# main_board.net
KiCad netlist of a schematic drawn in EAGLE
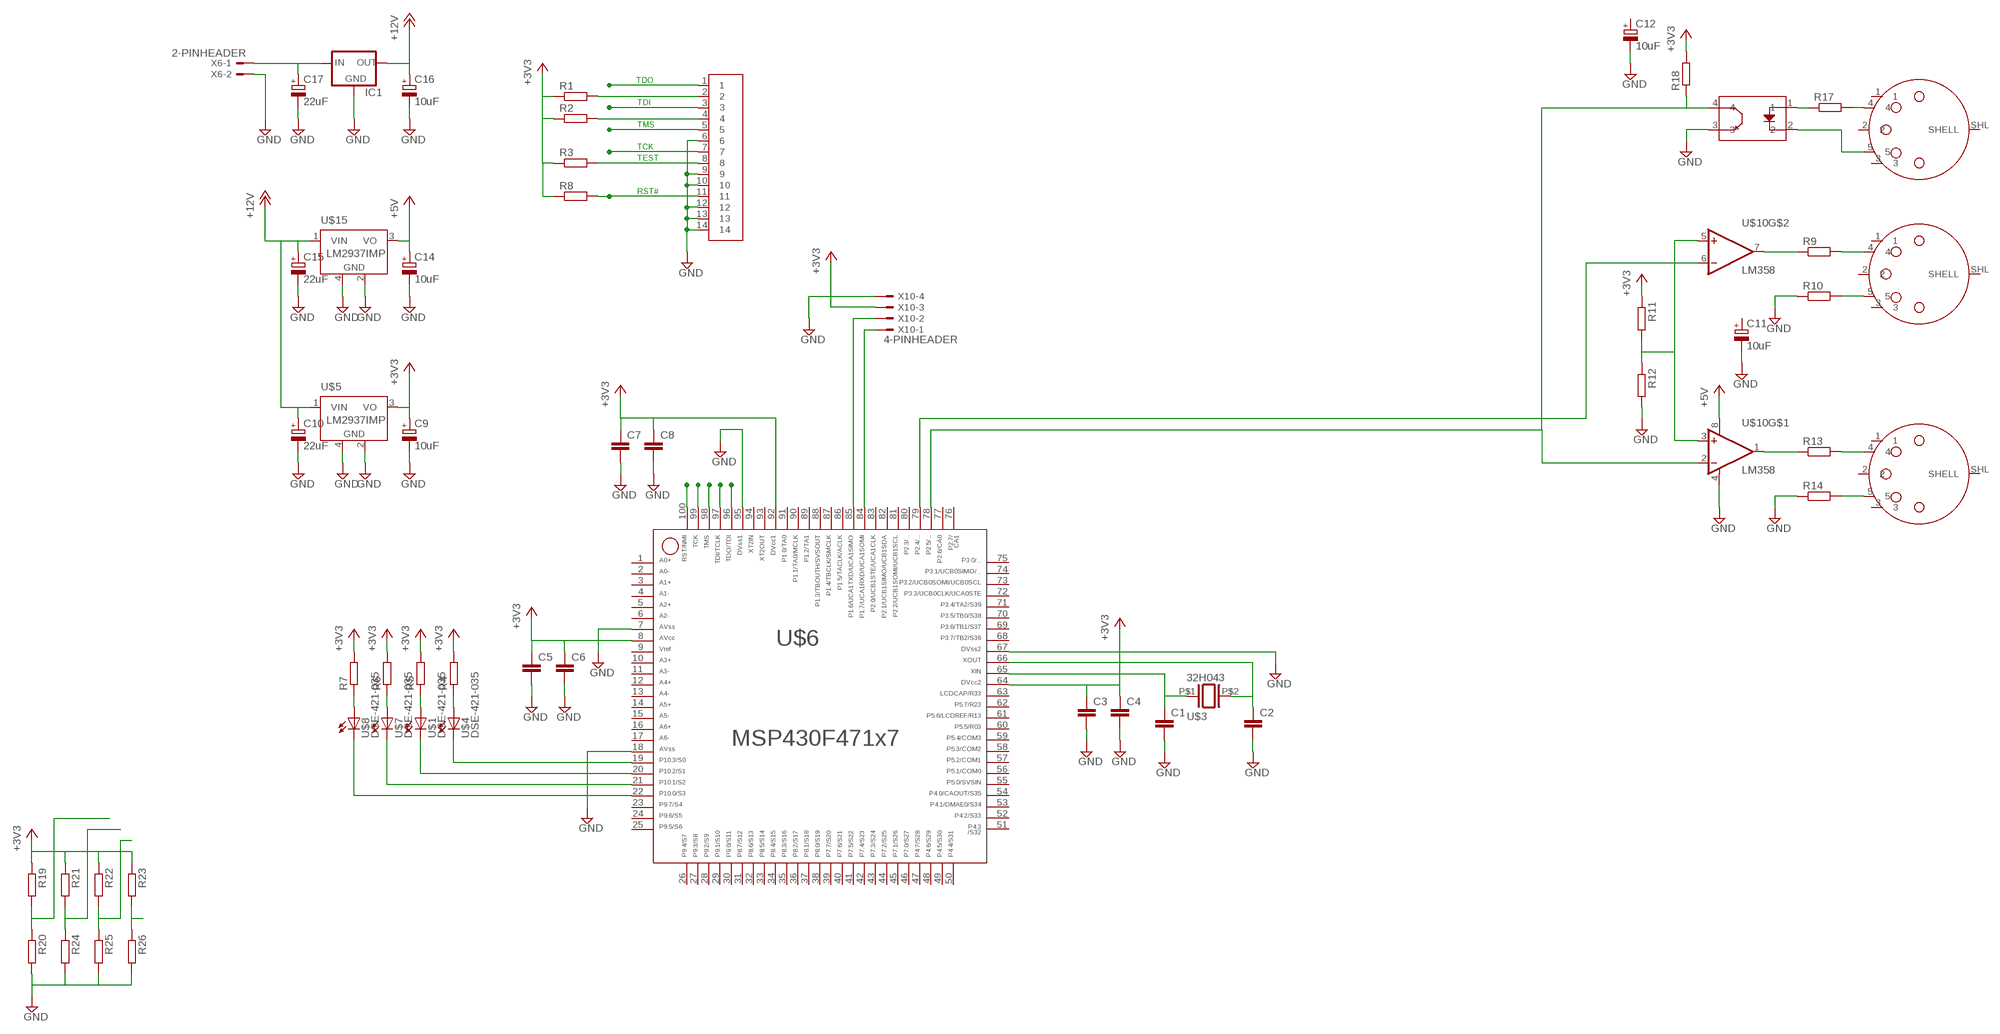
[diagram p0: schematic, sheet 1]

(export (version "E")
  (design (tool "Eeschema 10.0.6"))
  (components
    (comp (ref "C1")
      (value "C-EUC0402")
      (footprint "eagle-import:C0402")
      (libsource (lib "eagle-import") (part "C-EUC0402"))
    )
    (comp (ref "C2")
      (value "C-EUC0402")
      (footprint "eagle-import:C0402")
      (libsource (lib "eagle-import") (part "C-EUC0402"))
    )
    (comp (ref "C3")
      (value "C-EUC0402")
      (footprint "eagle-import:C0402")
      (libsource (lib "eagle-import") (part "C-EUC0402"))
    )
    (comp (ref "C4")
      (value "C-EUC0402")
      (footprint "eagle-import:C0402")
      (libsource (lib "eagle-import") (part "C-EUC0402"))
    )
    (comp (ref "C5")
      (value "C-EUC0402")
      (footprint "eagle-import:C0402")
      (libsource (lib "eagle-import") (part "C-EUC0402"))
    )
    (comp (ref "C6")
      (value "C-EUC0402")
      (footprint "eagle-import:C0402")
      (libsource (lib "eagle-import") (part "C-EUC0402"))
    )
    (comp (ref "C7")
      (value "C-EUC0402")
      (footprint "eagle-import:C0402")
      (libsource (lib "eagle-import") (part "C-EUC0402"))
    )
    (comp (ref "C8")
      (value "C-EUC0402")
      (footprint "eagle-import:C0402")
      (libsource (lib "eagle-import") (part "C-EUC0402"))
    )
    (comp (ref "C9")
      (value "10uF")
      (footprint "eagle-import:SMC_C")
      (libsource (lib "eagle-import") (part "CPOL-EUSMCC"))
    )
    (comp (ref "C10")
      (value "22uF")
      (footprint "eagle-import:SMC_D")
      (libsource (lib "eagle-import") (part "CPOL-EUSMCD"))
    )
    (comp (ref "C11")
      (value "10uF")
      (footprint "eagle-import:SMC_C")
      (libsource (lib "eagle-import") (part "CPOL-EUSMCC"))
    )
    (comp (ref "C12")
      (value "10uF")
      (footprint "eagle-import:SMC_C")
      (libsource (lib "eagle-import") (part "CPOL-EUSMCC"))
    )
    (comp (ref "C14")
      (value "10uF")
      (footprint "eagle-import:SMC_C")
      (libsource (lib "eagle-import") (part "CPOL-EUSMCC"))
    )
    (comp (ref "C15")
      (value "22uF")
      (footprint "eagle-import:SMC_D")
      (libsource (lib "eagle-import") (part "CPOL-EUSMCD"))
    )
    (comp (ref "C16")
      (value "10uF")
      (footprint "eagle-import:SMC_C")
      (libsource (lib "eagle-import") (part "CPOL-EUSMCC"))
    )
    (comp (ref "C17")
      (value "22uF")
      (footprint "eagle-import:SMC_D")
      (libsource (lib "eagle-import") (part "CPOL-EUSMCD"))
    )
    (comp (ref "IC1")
      (value "78MXXS")
      (footprint "eagle-import:78MXXS")
      (libsource (lib "eagle-import") (part "78MXXS"))
    )
    (comp (ref "R1")
      (value "R-EU_R0402")
      (footprint "eagle-import:R0402")
      (libsource (lib "eagle-import") (part "R-EU_R0402"))
    )
    (comp (ref "R2")
      (value "R-EU_R0402")
      (footprint "eagle-import:R0402")
      (libsource (lib "eagle-import") (part "R-EU_R0402"))
    )
    (comp (ref "R3")
      (value "R-EU_R0402")
      (footprint "eagle-import:R0402")
      (libsource (lib "eagle-import") (part "R-EU_R0402"))
    )
    (comp (ref "R4")
      (value "R-EU_R0402")
      (footprint "eagle-import:R0402")
      (libsource (lib "eagle-import") (part "R-EU_R0402"))
    )
    (comp (ref "R5")
      (value "R-EU_R0402")
      (footprint "eagle-import:R0402")
      (libsource (lib "eagle-import") (part "R-EU_R0402"))
    )
    (comp (ref "R6")
      (value "R-EU_R0402")
      (footprint "eagle-import:R0402")
      (libsource (lib "eagle-import") (part "R-EU_R0402"))
    )
    (comp (ref "R7")
      (value "R-EU_R0402")
      (footprint "eagle-import:R0402")
      (libsource (lib "eagle-import") (part "R-EU_R0402"))
    )
    (comp (ref "R8")
      (value "R-EU_R0402")
      (footprint "eagle-import:R0402")
      (libsource (lib "eagle-import") (part "R-EU_R0402"))
    )
    (comp (ref "R9")
      (value "R-EU_R1206")
      (footprint "eagle-import:R1206")
      (libsource (lib "eagle-import") (part "R-EU_R1206"))
    )
    (comp (ref "R10")
      (value "R-EU_R1206")
      (footprint "eagle-import:R1206")
      (libsource (lib "eagle-import") (part "R-EU_R1206"))
    )
    (comp (ref "R11")
      (value "R-EU_R0402")
      (footprint "eagle-import:R0402")
      (libsource (lib "eagle-import") (part "R-EU_R0402"))
    )
    (comp (ref "R12")
      (value "R-EU_R0402")
      (footprint "eagle-import:R0402")
      (libsource (lib "eagle-import") (part "R-EU_R0402"))
    )
    (comp (ref "R13")
      (value "R-EU_R1206")
      (footprint "eagle-import:R1206")
      (libsource (lib "eagle-import") (part "R-EU_R1206"))
    )
    (comp (ref "R14")
      (value "R-EU_R1206")
      (footprint "eagle-import:R1206")
      (libsource (lib "eagle-import") (part "R-EU_R1206"))
    )
    (comp (ref "R17")
      (value "R-EU_R1206")
      (footprint "eagle-import:R1206")
      (libsource (lib "eagle-import") (part "R-EU_R1206"))
    )
    (comp (ref "R18")
      (value "R-EU_R1206")
      (footprint "eagle-import:R1206")
      (libsource (lib "eagle-import") (part "R-EU_R1206"))
    )
    (comp (ref "R19")
      (value "R-EU_R0402")
      (footprint "eagle-import:R0402")
      (libsource (lib "eagle-import") (part "R-EU_R0402"))
    )
    (comp (ref "R20")
      (value "R-EU_R0402")
      (footprint "eagle-import:R0402")
      (libsource (lib "eagle-import") (part "R-EU_R0402"))
    )
    (comp (ref "R21")
      (value "R-EU_R0402")
      (footprint "eagle-import:R0402")
      (libsource (lib "eagle-import") (part "R-EU_R0402"))
    )
    (comp (ref "R22")
      (value "R-EU_R0402")
      (footprint "eagle-import:R0402")
      (libsource (lib "eagle-import") (part "R-EU_R0402"))
    )
    (comp (ref "R23")
      (value "R-EU_R0402")
      (footprint "eagle-import:R0402")
      (libsource (lib "eagle-import") (part "R-EU_R0402"))
    )
    (comp (ref "R24")
      (value "R-EU_R0402")
      (footprint "eagle-import:R0402")
      (libsource (lib "eagle-import") (part "R-EU_R0402"))
    )
    (comp (ref "R25")
      (value "R-EU_R0402")
      (footprint "eagle-import:R0402")
      (libsource (lib "eagle-import") (part "R-EU_R0402"))
    )
    (comp (ref "R26")
      (value "R-EU_R0402")
      (footprint "eagle-import:R0402")
      (libsource (lib "eagle-import") (part "R-EU_R0402"))
    )
    (comp (ref "U$1")
      (value "DSE-421-035")
      (footprint "eagle-import:2432")
      (libsource (lib "eagle-import") (part "DSE-421-035"))
    )
    (comp (ref "U$2")
      (value "2X7SMD_HEADER")
      (footprint "eagle-import:2X14SMDPADS")
      (libsource (lib "eagle-import") (part "2X7SMD_HEADER"))
    )
    (comp (ref "U$3")
      (value "32H043")
      (footprint "eagle-import:XTAL-SMALL-4")
      (libsource (lib "eagle-import") (part "32H043"))
    )
    (comp (ref "U$4")
      (value "DSE-421-035")
      (footprint "eagle-import:2432")
      (libsource (lib "eagle-import") (part "DSE-421-035"))
    )
    (comp (ref "U$5")
      (value "LM2937IMP")
      (footprint "eagle-import:SOT223")
      (libsource (lib "eagle-import") (part "LM2937IMP"))
    )
    (comp (ref "U$6")
      (value "F471X7---PZ100")
      (footprint "eagle-import:PZ100")
      (libsource (lib "eagle-import") (part "F471X7---PZ100"))
    )
    (comp (ref "U$7")
      (value "DSE-421-035")
      (footprint "eagle-import:2432")
      (libsource (lib "eagle-import") (part "DSE-421-035"))
    )
    (comp (ref "U$8")
      (value "DSE-421-035")
      (footprint "eagle-import:2432")
      (libsource (lib "eagle-import") (part "DSE-421-035"))
    )
    (comp (ref "U$9")
      (value "MIDI_VERT")
      (footprint "eagle-import:DIN-5_VERT")
      (libsource (lib "eagle-import") (part "MIDI_VERT"))
    )
    (comp (ref "U$10")
      (value "LM358")
      (footprint "eagle-import:SO08")
      (libsource (lib "eagle-import") (part "LM358"))
    )
    (comp (ref "U$11")
      (value "MIDI_VERT")
      (footprint "eagle-import:DIN-5_VERT")
      (libsource (lib "eagle-import") (part "MIDI_VERT"))
    )
    (comp (ref "U$15")
      (value "LM2937IMP")
      (footprint "eagle-import:SOT223")
      (libsource (lib "eagle-import") (part "LM2937IMP"))
    )
    (comp (ref "U$19")
      (value "F2801A")
      (footprint "eagle-import:LONG_TSOP")
      (libsource (lib "eagle-import") (part "F2801A"))
    )
    (comp (ref "U$20")
      (value "MIDI_VERT")
      (footprint "eagle-import:DIN-5_VERT")
      (libsource (lib "eagle-import") (part "MIDI_VERT"))
    )
    (comp (ref "X6")
      (value "2-PINHEADER")
      (footprint "eagle-import:22-23-2021")
      (fields (field (name "MF") "MOLEX") (field (name "MPN") "22-23-2021"))
      (libsource (lib "eagle-import") (part "2-PINHEADER"))
    )
    (comp (ref "X10")
      (value "4-PINHEADER")
      (footprint "eagle-import:22-23-2041")
      (fields (field (name "MF") "MOLEX") (field (name "MPN") "22-23-2041"))
      (libsource (lib "eagle-import") (part "4-PINHEADER"))
    )
  )
  (nets
    (net (code "1") (name "+3V3") (class "Default")
      (node (ref "C3") (pin "1") (pinfunction "1_1") (pintype "passive"))
      (node (ref "C4") (pin "1") (pinfunction "1_1") (pintype "passive"))
      (node (ref "C5") (pin "1") (pinfunction "1_1") (pintype "passive"))
      (node (ref "C6") (pin "1") (pinfunction "1_1") (pintype "passive"))
      (node (ref "C7") (pin "1") (pinfunction "1_1") (pintype "passive"))
      (node (ref "C8") (pin "1") (pinfunction "1_1") (pintype "passive"))
      (node (ref "C9") (pin "+") (pinfunction "+_+") (pintype "passive"))
      (node (ref "R1") (pin "1") (pinfunction "1_1") (pintype "passive"))
      (node (ref "R11") (pin "1") (pinfunction "1_1") (pintype "passive"))
      (node (ref "R18") (pin "2") (pinfunction "2_2") (pintype "passive"))
      (node (ref "R19") (pin "1") (pinfunction "1_1") (pintype "passive"))
      (node (ref "R2") (pin "1") (pinfunction "1_1") (pintype "passive"))
      (node (ref "R21") (pin "1") (pinfunction "1_1") (pintype "passive"))
      (node (ref "R22") (pin "1") (pinfunction "1_1") (pintype "passive"))
      (node (ref "R23") (pin "1") (pinfunction "1_1") (pintype "passive"))
      (node (ref "R3") (pin "1") (pinfunction "1_1") (pintype "passive"))
      (node (ref "R4") (pin "2") (pinfunction "2_2") (pintype "passive"))
      (node (ref "R5") (pin "2") (pinfunction "2_2") (pintype "passive"))
      (node (ref "R6") (pin "2") (pinfunction "2_2") (pintype "passive"))
      (node (ref "R7") (pin "2") (pinfunction "2_2") (pintype "passive"))
      (node (ref "R8") (pin "1") (pinfunction "1_1") (pintype "passive"))
      (node (ref "U$5") (pin "3") (pinfunction "VO_3") (pintype "passive"))
      (node (ref "U$6") (pin "64") (pinfunction "64_64") (pintype "power_in"))
      (node (ref "U$6") (pin "8") (pinfunction "8_8") (pintype "input"))
      (node (ref "U$6") (pin "92") (pinfunction "92_92") (pintype "power_in"))
      (node (ref "X10") (pin "3") (pinfunction "S_3") (pintype "passive"))
    )
    (net (code "2") (name "+5V") (class "Default")
      (node (ref "C14") (pin "+") (pinfunction "+_+") (pintype "passive"))
      (node (ref "U$10") (pin "8") (pinfunction "V+_8") (pintype "power_in"))
      (node (ref "U$15") (pin "3") (pinfunction "VO_3") (pintype "passive"))
    )
    (net (code "3") (name "+12V") (class "Default")
      (node (ref "C10") (pin "+") (pinfunction "+_+") (pintype "passive"))
      (node (ref "C15") (pin "+") (pinfunction "+_+") (pintype "passive"))
      (node (ref "C16") (pin "+") (pinfunction "+_+") (pintype "passive"))
      (node (ref "IC1") (pin "OUT") (pinfunction "OUT_OUT") (pintype "passive"))
      (node (ref "U$15") (pin "1") (pinfunction "VIN_1") (pintype "input"))
      (node (ref "U$5") (pin "1") (pinfunction "VIN_1") (pintype "input"))
    )
    (net (code "4") (name "/RST#") (class "Default")
      (node (ref "R8") (pin "2") (pinfunction "2_2") (pintype "passive"))
      (node (ref "U$2") (pin "11") (pinfunction "11_11") (pintype "input"))
      (node (ref "U$6") (pin "100") (pinfunction "100_100") (pintype "input"))
    )
    (net (code "5") (name "/TCK") (class "Default")
      (node (ref "U$2") (pin "7") (pinfunction "7_7") (pintype "input"))
      (node (ref "U$6") (pin "99") (pinfunction "99_99") (pintype "input"))
    )
    (net (code "6") (name "/TDI") (class "Default")
      (node (ref "U$2") (pin "3") (pinfunction "3_3") (pintype "input"))
      (node (ref "U$6") (pin "97") (pinfunction "97_97") (pintype "input"))
    )
    (net (code "7") (name "/TDO") (class "Default")
      (node (ref "U$2") (pin "1") (pinfunction "1_1") (pintype "input"))
      (node (ref "U$6") (pin "96") (pinfunction "96_96") (pintype "bidirectional"))
    )
    (net (code "8") (name "/TMS") (class "Default")
      (node (ref "U$2") (pin "5") (pinfunction "5_5") (pintype "input"))
      (node (ref "U$6") (pin "98") (pinfunction "98_98") (pintype "input"))
    )
    (net (code "9") (name "GND") (class "Default")
      (node (ref "C1") (pin "2") (pinfunction "2_2") (pintype "passive"))
      (node (ref "C10") (pin "-") (pinfunction "-_-") (pintype "passive"))
      (node (ref "C11") (pin "-") (pinfunction "-_-") (pintype "passive"))
      (node (ref "C12") (pin "-") (pinfunction "-_-") (pintype "passive"))
      (node (ref "C14") (pin "-") (pinfunction "-_-") (pintype "passive"))
      (node (ref "C15") (pin "-") (pinfunction "-_-") (pintype "passive"))
      (node (ref "C16") (pin "-") (pinfunction "-_-") (pintype "passive"))
      (node (ref "C17") (pin "-") (pinfunction "-_-") (pintype "passive"))
      (node (ref "C2") (pin "2") (pinfunction "2_2") (pintype "passive"))
      (node (ref "C3") (pin "2") (pinfunction "2_2") (pintype "passive"))
      (node (ref "C4") (pin "2") (pinfunction "2_2") (pintype "passive"))
      (node (ref "C5") (pin "2") (pinfunction "2_2") (pintype "passive"))
      (node (ref "C6") (pin "2") (pinfunction "2_2") (pintype "passive"))
      (node (ref "C7") (pin "2") (pinfunction "2_2") (pintype "passive"))
      (node (ref "C8") (pin "2") (pinfunction "2_2") (pintype "passive"))
      (node (ref "C9") (pin "-") (pinfunction "-_-") (pintype "passive"))
      (node (ref "IC1") (pin "GND") (pinfunction "GND_GND") (pintype "input"))
      (node (ref "R10") (pin "1") (pinfunction "1_1") (pintype "passive"))
      (node (ref "R12") (pin "2") (pinfunction "2_2") (pintype "passive"))
      (node (ref "R14") (pin "1") (pinfunction "1_1") (pintype "passive"))
      (node (ref "R20") (pin "2") (pinfunction "2_2") (pintype "passive"))
      (node (ref "R24") (pin "2") (pinfunction "2_2") (pintype "passive"))
      (node (ref "R25") (pin "2") (pinfunction "2_2") (pintype "passive"))
      (node (ref "R26") (pin "2") (pinfunction "2_2") (pintype "passive"))
      (node (ref "U$10") (pin "4") (pinfunction "V-_4") (pintype "power_in"))
      (node (ref "U$15") (pin "2") (pinfunction "GND_2") (pintype "passive"))
      (node (ref "U$15") (pin "4") (pinfunction "GND_4") (pintype "passive"))
      (node (ref "U$19") (pin "3") (pinfunction "3_3") (pintype "bidirectional"))
      (node (ref "U$2") (pin "10") (pinfunction "10_10") (pintype "input"))
      (node (ref "U$2") (pin "12") (pinfunction "12_12") (pintype "input"))
      (node (ref "U$2") (pin "13") (pinfunction "13_13") (pintype "input"))
      (node (ref "U$2") (pin "14") (pinfunction "14_14") (pintype "input"))
      (node (ref "U$2") (pin "6") (pinfunction "6_6") (pintype "input"))
      (node (ref "U$2") (pin "9") (pinfunction "9_9") (pintype "input"))
      (node (ref "U$5") (pin "2") (pinfunction "GND_2") (pintype "passive"))
      (node (ref "U$5") (pin "4") (pinfunction "GND_4") (pintype "passive"))
      (node (ref "U$6") (pin "18") (pinfunction "18_18") (pintype "power_in"))
      (node (ref "U$6") (pin "67") (pinfunction "67_67") (pintype "power_in"))
      (node (ref "U$6") (pin "7") (pinfunction "7_7") (pintype "input"))
      (node (ref "U$6") (pin "95") (pinfunction "95_95") (pintype "power_in"))
      (node (ref "X10") (pin "4") (pinfunction "S_4") (pintype "passive"))
      (node (ref "X6") (pin "2") (pinfunction "S_2") (pintype "passive"))
    )
    (net (code "10") (name "Net-(R1-Pad2)") (class "Default")
      (node (ref "R1") (pin "2") (pinfunction "2_2") (pintype "passive"))
      (node (ref "U$2") (pin "2") (pinfunction "2_2") (pintype "input"))
    )
    (net (code "11") (name "Net-(R2-Pad2)") (class "Default")
      (node (ref "R2") (pin "2") (pinfunction "2_2") (pintype "passive"))
      (node (ref "U$2") (pin "4") (pinfunction "4_4") (pintype "input"))
    )
    (net (code "12") (name "Net-(R3-Pad2)") (class "Default")
      (node (ref "R3") (pin "2") (pinfunction "2_2") (pintype "passive"))
      (node (ref "U$2") (pin "8") (pinfunction "8_8") (pintype "input"))
    )
    (net (code "13") (name "Net-(R9-Pad2)") (class "Default")
      (node (ref "R9") (pin "2") (pinfunction "2_2") (pintype "passive"))
      (node (ref "U$9") (pin "4") (pinfunction "4_4") (pintype "input"))
    )
    (net (code "14") (name "Net-(R10-Pad2)") (class "Default")
      (node (ref "R10") (pin "2") (pinfunction "2_2") (pintype "passive"))
      (node (ref "U$9") (pin "5") (pinfunction "5_5") (pintype "input"))
    )
    (net (code "15") (name "Net-(R13-Pad2)") (class "Default")
      (node (ref "R13") (pin "2") (pinfunction "2_2") (pintype "passive"))
      (node (ref "U$11") (pin "4") (pinfunction "4_4") (pintype "input"))
    )
    (net (code "16") (name "Net-(R14-Pad2)") (class "Default")
      (node (ref "R14") (pin "2") (pinfunction "2_2") (pintype "passive"))
      (node (ref "U$11") (pin "5") (pinfunction "5_5") (pintype "input"))
    )
    (net (code "17") (name "Net-(R17-Pad1)") (class "Default")
      (node (ref "R17") (pin "1") (pinfunction "1_1") (pintype "passive"))
      (node (ref "U$19") (pin "1") (pinfunction "1_1") (pintype "bidirectional"))
    )
    (net (code "18") (name "Net-(R17-Pad2)") (class "Default")
      (node (ref "R17") (pin "2") (pinfunction "2_2") (pintype "passive"))
      (node (ref "U$20") (pin "4") (pinfunction "4_4") (pintype "input"))
    )
    (net (code "19") (name "Net-(R19-Pad2)") (class "Default")
      (node (ref "R19") (pin "2") (pinfunction "2_2") (pintype "passive"))
      (node (ref "R20") (pin "1") (pinfunction "1_1") (pintype "passive"))
    )
    (net (code "20") (name "Net-(R21-Pad2)") (class "Default")
      (node (ref "R21") (pin "2") (pinfunction "2_2") (pintype "passive"))
      (node (ref "R24") (pin "1") (pinfunction "1_1") (pintype "passive"))
    )
    (net (code "21") (name "Net-(R22-Pad2)") (class "Default")
      (node (ref "R22") (pin "2") (pinfunction "2_2") (pintype "passive"))
      (node (ref "R25") (pin "1") (pinfunction "1_1") (pintype "passive"))
    )
    (net (code "22") (name "Net-(R23-Pad2)") (class "Default")
      (node (ref "R23") (pin "2") (pinfunction "2_2") (pintype "passive"))
      (node (ref "R26") (pin "1") (pinfunction "1_1") (pintype "passive"))
    )
    (net (code "23") (name "Net-(U$1-A)") (class "Default")
      (node (ref "R5") (pin "1") (pinfunction "1_1") (pintype "passive"))
      (node (ref "U$1") (pin "P$1") (pinfunction "A_P$1") (pintype "passive"))
    )
    (net (code "24") (name "Net-(U$1-C)") (class "Default")
      (node (ref "U$1") (pin "MARKED") (pinfunction "C_MARKED") (pintype "passive"))
      (node (ref "U$6") (pin "20") (pinfunction "20_20") (pintype "bidirectional"))
    )
    (net (code "25") (name "Net-(U$3-1)") (class "Default")
      (node (ref "C1") (pin "1") (pinfunction "1_1") (pintype "passive"))
      (node (ref "U$3") (pin "P$1") (pinfunction "1_P$1") (pintype "bidirectional"))
      (node (ref "U$6") (pin "65") (pinfunction "65_65") (pintype "input"))
    )
    (net (code "26") (name "Net-(U$3-2)") (class "Default")
      (node (ref "C2") (pin "1") (pinfunction "1_1") (pintype "passive"))
      (node (ref "U$3") (pin "P$2") (pinfunction "2_P$2") (pintype "bidirectional"))
      (node (ref "U$6") (pin "66") (pinfunction "66_66") (pintype "output"))
    )
    (net (code "27") (name "Net-(U$4-A)") (class "Default")
      (node (ref "R4") (pin "1") (pinfunction "1_1") (pintype "passive"))
      (node (ref "U$4") (pin "P$1") (pinfunction "A_P$1") (pintype "passive"))
    )
    (net (code "28") (name "Net-(U$4-C)") (class "Default")
      (node (ref "U$4") (pin "MARKED") (pinfunction "C_MARKED") (pintype "passive"))
      (node (ref "U$6") (pin "19") (pinfunction "19_19") (pintype "bidirectional"))
    )
    (net (code "29") (name "Net-(U$7-A)") (class "Default")
      (node (ref "R6") (pin "1") (pinfunction "1_1") (pintype "passive"))
      (node (ref "U$7") (pin "P$1") (pinfunction "A_P$1") (pintype "passive"))
    )
    (net (code "30") (name "Net-(U$7-C)") (class "Default")
      (node (ref "U$6") (pin "21") (pinfunction "21_21") (pintype "bidirectional"))
      (node (ref "U$7") (pin "MARKED") (pinfunction "C_MARKED") (pintype "passive"))
    )
    (net (code "31") (name "Net-(U$8-A)") (class "Default")
      (node (ref "R7") (pin "1") (pinfunction "1_1") (pintype "passive"))
      (node (ref "U$8") (pin "P$1") (pinfunction "A_P$1") (pintype "passive"))
    )
    (net (code "32") (name "Net-(U$8-C)") (class "Default")
      (node (ref "U$6") (pin "22") (pinfunction "22_22") (pintype "bidirectional"))
      (node (ref "U$8") (pin "MARKED") (pinfunction "C_MARKED") (pintype "passive"))
    )
    (net (code "33") (name "Net-(U$10A-+IN)") (class "Default")
      (node (ref "R11") (pin "2") (pinfunction "2_2") (pintype "passive"))
      (node (ref "R12") (pin "1") (pinfunction "1_1") (pintype "passive"))
      (node (ref "U$10") (pin "3") (pinfunction "+IN_3") (pintype "input"))
      (node (ref "U$10") (pin "5") (pinfunction "+IN_5") (pintype "input"))
    )
    (net (code "34") (name "Net-(U$10A--IN)") (class "Default")
      (node (ref "R18") (pin "1") (pinfunction "1_1") (pintype "passive"))
      (node (ref "U$10") (pin "2") (pinfunction "-IN_2") (pintype "input"))
      (node (ref "U$19") (pin "4") (pinfunction "4_4") (pintype "bidirectional"))
      (node (ref "U$6") (pin "78") (pinfunction "78_78") (pintype "bidirectional"))
    )
    (net (code "35") (name "Net-(U$10A-OUT)") (class "Default")
      (node (ref "R13") (pin "1") (pinfunction "1_1") (pintype "passive"))
      (node (ref "U$10") (pin "1") (pinfunction "OUT_1") (pintype "output"))
    )
    (net (code "36") (name "Net-(U$10B--IN)") (class "Default")
      (node (ref "U$10") (pin "6") (pinfunction "-IN_6") (pintype "input"))
      (node (ref "U$6") (pin "79") (pinfunction "79_79") (pintype "bidirectional"))
    )
    (net (code "37") (name "Net-(U$10B-OUT)") (class "Default")
      (node (ref "R9") (pin "1") (pinfunction "1_1") (pintype "passive"))
      (node (ref "U$10") (pin "7") (pinfunction "OUT_7") (pintype "output"))
    )
    (net (code "38") (name "Net-(U$19-Pad2)") (class "Default")
      (node (ref "U$19") (pin "2") (pinfunction "2_2") (pintype "bidirectional"))
      (node (ref "U$20") (pin "5") (pinfunction "5_5") (pintype "input"))
    )
    (net (code "39") (name "Net-(X6A-S)") (class "Default")
      (node (ref "C17") (pin "+") (pinfunction "+_+") (pintype "passive"))
      (node (ref "IC1") (pin "IN") (pinfunction "IN_IN") (pintype "input"))
      (node (ref "X6") (pin "1") (pinfunction "S_1") (pintype "passive"))
    )
    (net (code "40") (name "Net-(X10A-S)") (class "Default")
      (node (ref "U$6") (pin "84") (pinfunction "84_84") (pintype "bidirectional"))
      (node (ref "X10") (pin "1") (pinfunction "S_1") (pintype "passive"))
    )
    (net (code "41") (name "Net-(X10B-S)") (class "Default")
      (node (ref "U$6") (pin "85") (pinfunction "85_85") (pintype "bidirectional"))
      (node (ref "X10") (pin "2") (pinfunction "S_2") (pintype "passive"))
    )
    (net (code "42") (name "unconnected-(C11-Pad+)") (class "Default")
      (node (ref "C11") (pin "+") (pinfunction "+_+") (pintype "passive"))
    )
    (net (code "43") (name "unconnected-(C12-Pad+)") (class "Default")
      (node (ref "C12") (pin "+") (pinfunction "+_+") (pintype "passive"))
    )
    (net (code "44") (name "unconnected-(U$6-Pad1)") (class "Default")
      (node (ref "U$6") (pin "1") (pinfunction "1_1") (pintype "input"))
    )
    (net (code "45") (name "unconnected-(U$6-Pad2)") (class "Default")
      (node (ref "U$6") (pin "2") (pinfunction "2_2") (pintype "input"))
    )
    (net (code "46") (name "unconnected-(U$6-Pad3)") (class "Default")
      (node (ref "U$6") (pin "3") (pinfunction "3_3") (pintype "input"))
    )
    (net (code "47") (name "unconnected-(U$6-Pad4)") (class "Default")
      (node (ref "U$6") (pin "4") (pinfunction "4_4") (pintype "input"))
    )
    (net (code "48") (name "unconnected-(U$6-Pad5)") (class "Default")
      (node (ref "U$6") (pin "5") (pinfunction "5_5") (pintype "input"))
    )
    (net (code "49") (name "unconnected-(U$6-Pad6)") (class "Default")
      (node (ref "U$6") (pin "6") (pinfunction "6_6") (pintype "input"))
    )
    (net (code "50") (name "unconnected-(U$6-Pad9)") (class "Default")
      (node (ref "U$6") (pin "9") (pinfunction "9_9") (pintype "bidirectional"))
    )
    (net (code "51") (name "unconnected-(U$6-Pad10)") (class "Default")
      (node (ref "U$6") (pin "10") (pinfunction "10_10") (pintype "input"))
    )
    (net (code "52") (name "unconnected-(U$6-Pad11)") (class "Default")
      (node (ref "U$6") (pin "11") (pinfunction "11_11") (pintype "input"))
    )
    (net (code "53") (name "unconnected-(U$6-Pad12)") (class "Default")
      (node (ref "U$6") (pin "12") (pinfunction "12_12") (pintype "input"))
    )
    (net (code "54") (name "unconnected-(U$6-Pad13)") (class "Default")
      (node (ref "U$6") (pin "13") (pinfunction "13_13") (pintype "input"))
    )
    (net (code "55") (name "unconnected-(U$6-Pad14)") (class "Default")
      (node (ref "U$6") (pin "14") (pinfunction "14_14") (pintype "input"))
    )
    (net (code "56") (name "unconnected-(U$6-Pad15)") (class "Default")
      (node (ref "U$6") (pin "15") (pinfunction "15_15") (pintype "input"))
    )
    (net (code "57") (name "unconnected-(U$6-Pad16)") (class "Default")
      (node (ref "U$6") (pin "16") (pinfunction "16_16") (pintype "input"))
    )
    (net (code "58") (name "unconnected-(U$6-Pad17)") (class "Default")
      (node (ref "U$6") (pin "17") (pinfunction "17_17") (pintype "input"))
    )
    (net (code "59") (name "unconnected-(U$6-Pad23)") (class "Default")
      (node (ref "U$6") (pin "23") (pinfunction "23_23") (pintype "bidirectional"))
    )
    (net (code "60") (name "unconnected-(U$6-Pad24)") (class "Default")
      (node (ref "U$6") (pin "24") (pinfunction "24_24") (pintype "bidirectional"))
    )
    (net (code "61") (name "unconnected-(U$6-Pad25)") (class "Default")
      (node (ref "U$6") (pin "25") (pinfunction "25_25") (pintype "bidirectional"))
    )
    (net (code "62") (name "unconnected-(U$6-Pad26)") (class "Default")
      (node (ref "U$6") (pin "26") (pinfunction "26_26") (pintype "bidirectional"))
    )
    (net (code "63") (name "unconnected-(U$6-Pad27)") (class "Default")
      (node (ref "U$6") (pin "27") (pinfunction "27_27") (pintype "bidirectional"))
    )
    (net (code "64") (name "unconnected-(U$6-Pad28)") (class "Default")
      (node (ref "U$6") (pin "28") (pinfunction "28_28") (pintype "bidirectional"))
    )
    (net (code "65") (name "unconnected-(U$6-Pad29)") (class "Default")
      (node (ref "U$6") (pin "29") (pinfunction "29_29") (pintype "bidirectional"))
    )
    (net (code "66") (name "unconnected-(U$6-Pad30)") (class "Default")
      (node (ref "U$6") (pin "30") (pinfunction "30_30") (pintype "bidirectional"))
    )
    (net (code "67") (name "unconnected-(U$6-Pad31)") (class "Default")
      (node (ref "U$6") (pin "31") (pinfunction "31_31") (pintype "bidirectional"))
    )
    (net (code "68") (name "unconnected-(U$6-Pad32)") (class "Default")
      (node (ref "U$6") (pin "32") (pinfunction "32_32") (pintype "bidirectional"))
    )
    (net (code "69") (name "unconnected-(U$6-Pad33)") (class "Default")
      (node (ref "U$6") (pin "33") (pinfunction "33_33") (pintype "bidirectional"))
    )
    (net (code "70") (name "unconnected-(U$6-Pad34)") (class "Default")
      (node (ref "U$6") (pin "34") (pinfunction "34_34") (pintype "bidirectional"))
    )
    (net (code "71") (name "unconnected-(U$6-Pad35)") (class "Default")
      (node (ref "U$6") (pin "35") (pinfunction "35_35") (pintype "bidirectional"))
    )
    (net (code "72") (name "unconnected-(U$6-Pad36)") (class "Default")
      (node (ref "U$6") (pin "36") (pinfunction "36_36") (pintype "bidirectional"))
    )
    (net (code "73") (name "unconnected-(U$6-Pad37)") (class "Default")
      (node (ref "U$6") (pin "37") (pinfunction "37_37") (pintype "bidirectional"))
    )
    (net (code "74") (name "unconnected-(U$6-Pad38)") (class "Default")
      (node (ref "U$6") (pin "38") (pinfunction "38_38") (pintype "bidirectional"))
    )
    (net (code "75") (name "unconnected-(U$6-Pad39)") (class "Default")
      (node (ref "U$6") (pin "39") (pinfunction "39_39") (pintype "bidirectional"))
    )
    (net (code "76") (name "unconnected-(U$6-Pad40)") (class "Default")
      (node (ref "U$6") (pin "40") (pinfunction "40_40") (pintype "bidirectional"))
    )
    (net (code "77") (name "unconnected-(U$6-Pad41)") (class "Default")
      (node (ref "U$6") (pin "41") (pinfunction "41_41") (pintype "bidirectional"))
    )
    (net (code "78") (name "unconnected-(U$6-Pad42)") (class "Default")
      (node (ref "U$6") (pin "42") (pinfunction "42_42") (pintype "bidirectional"))
    )
    (net (code "79") (name "unconnected-(U$6-Pad43)") (class "Default")
      (node (ref "U$6") (pin "43") (pinfunction "43_43") (pintype "bidirectional"))
    )
    (net (code "80") (name "unconnected-(U$6-Pad44)") (class "Default")
      (node (ref "U$6") (pin "44") (pinfunction "44_44") (pintype "bidirectional"))
    )
    (net (code "81") (name "unconnected-(U$6-Pad45)") (class "Default")
      (node (ref "U$6") (pin "45") (pinfunction "45_45") (pintype "bidirectional"))
    )
    (net (code "82") (name "unconnected-(U$6-Pad46)") (class "Default")
      (node (ref "U$6") (pin "46") (pinfunction "46_46") (pintype "bidirectional"))
    )
    (net (code "83") (name "unconnected-(U$6-Pad47)") (class "Default")
      (node (ref "U$6") (pin "47") (pinfunction "47_47") (pintype "bidirectional"))
    )
    (net (code "84") (name "unconnected-(U$6-Pad48)") (class "Default")
      (node (ref "U$6") (pin "48") (pinfunction "48_48") (pintype "bidirectional"))
    )
    (net (code "85") (name "unconnected-(U$6-Pad49)") (class "Default")
      (node (ref "U$6") (pin "49") (pinfunction "49_49") (pintype "bidirectional"))
    )
    (net (code "86") (name "unconnected-(U$6-Pad50)") (class "Default")
      (node (ref "U$6") (pin "50") (pinfunction "50_50") (pintype "bidirectional"))
    )
    (net (code "87") (name "unconnected-(U$6-Pad51)") (class "Default")
      (node (ref "U$6") (pin "51") (pinfunction "51_51") (pintype "bidirectional"))
    )
    (net (code "88") (name "unconnected-(U$6-Pad52)") (class "Default")
      (node (ref "U$6") (pin "52") (pinfunction "52_52") (pintype "bidirectional"))
    )
    (net (code "89") (name "unconnected-(U$6-Pad53)") (class "Default")
      (node (ref "U$6") (pin "53") (pinfunction "53_53") (pintype "bidirectional"))
    )
    (net (code "90") (name "unconnected-(U$6-Pad54)") (class "Default")
      (node (ref "U$6") (pin "54") (pinfunction "54_54") (pintype "bidirectional"))
    )
    (net (code "91") (name "unconnected-(U$6-Pad55)") (class "Default")
      (node (ref "U$6") (pin "55") (pinfunction "55_55") (pintype "bidirectional"))
    )
    (net (code "92") (name "unconnected-(U$6-Pad56)") (class "Default")
      (node (ref "U$6") (pin "56") (pinfunction "56_56") (pintype "bidirectional"))
    )
    (net (code "93") (name "unconnected-(U$6-Pad57)") (class "Default")
      (node (ref "U$6") (pin "57") (pinfunction "57_57") (pintype "bidirectional"))
    )
    (net (code "94") (name "unconnected-(U$6-Pad58)") (class "Default")
      (node (ref "U$6") (pin "58") (pinfunction "58_58") (pintype "bidirectional"))
    )
    (net (code "95") (name "unconnected-(U$6-Pad59)") (class "Default")
      (node (ref "U$6") (pin "59") (pinfunction "59_59") (pintype "bidirectional"))
    )
    (net (code "96") (name "unconnected-(U$6-Pad60)") (class "Default")
      (node (ref "U$6") (pin "60") (pinfunction "60_60") (pintype "bidirectional"))
    )
    (net (code "97") (name "unconnected-(U$6-Pad61)") (class "Default")
      (node (ref "U$6") (pin "61") (pinfunction "61_61") (pintype "bidirectional"))
    )
    (net (code "98") (name "unconnected-(U$6-Pad62)") (class "Default")
      (node (ref "U$6") (pin "62") (pinfunction "62_62") (pintype "bidirectional"))
    )
    (net (code "99") (name "unconnected-(U$6-Pad63)") (class "Default")
      (node (ref "U$6") (pin "63") (pinfunction "63_63") (pintype "input"))
    )
    (net (code "100") (name "unconnected-(U$6-Pad68)") (class "Default")
      (node (ref "U$6") (pin "68") (pinfunction "68_68") (pintype "bidirectional"))
    )
    (net (code "101") (name "unconnected-(U$6-Pad69)") (class "Default")
      (node (ref "U$6") (pin "69") (pinfunction "69_69") (pintype "bidirectional"))
    )
    (net (code "102") (name "unconnected-(U$6-Pad70)") (class "Default")
      (node (ref "U$6") (pin "70") (pinfunction "70_70") (pintype "bidirectional"))
    )
    (net (code "103") (name "unconnected-(U$6-Pad71)") (class "Default")
      (node (ref "U$6") (pin "71") (pinfunction "71_71") (pintype "bidirectional"))
    )
    (net (code "104") (name "unconnected-(U$6-Pad72)") (class "Default")
      (node (ref "U$6") (pin "72") (pinfunction "72_72") (pintype "bidirectional"))
    )
    (net (code "105") (name "unconnected-(U$6-Pad73)") (class "Default")
      (node (ref "U$6") (pin "73") (pinfunction "73_73") (pintype "bidirectional"))
    )
    (net (code "106") (name "unconnected-(U$6-Pad74)") (class "Default")
      (node (ref "U$6") (pin "74") (pinfunction "74_74") (pintype "bidirectional"))
    )
    (net (code "107") (name "unconnected-(U$6-Pad75)") (class "Default")
      (node (ref "U$6") (pin "75") (pinfunction "75_75") (pintype "bidirectional"))
    )
    (net (code "108") (name "unconnected-(U$6-Pad76)") (class "Default")
      (node (ref "U$6") (pin "76") (pinfunction "76_76") (pintype "bidirectional"))
    )
    (net (code "109") (name "unconnected-(U$6-Pad77)") (class "Default")
      (node (ref "U$6") (pin "77") (pinfunction "77_77") (pintype "bidirectional"))
    )
    (net (code "110") (name "unconnected-(U$6-Pad80)") (class "Default")
      (node (ref "U$6") (pin "80") (pinfunction "80_80") (pintype "bidirectional"))
    )
    (net (code "111") (name "unconnected-(U$6-Pad81)") (class "Default")
      (node (ref "U$6") (pin "81") (pinfunction "81_81") (pintype "bidirectional"))
    )
    (net (code "112") (name "unconnected-(U$6-Pad82)") (class "Default")
      (node (ref "U$6") (pin "82") (pinfunction "82_82") (pintype "bidirectional"))
    )
    (net (code "113") (name "unconnected-(U$6-Pad83)") (class "Default")
      (node (ref "U$6") (pin "83") (pinfunction "83_83") (pintype "bidirectional"))
    )
    (net (code "114") (name "unconnected-(U$6-Pad86)") (class "Default")
      (node (ref "U$6") (pin "86") (pinfunction "86_86") (pintype "bidirectional"))
    )
    (net (code "115") (name "unconnected-(U$6-Pad87)") (class "Default")
      (node (ref "U$6") (pin "87") (pinfunction "87_87") (pintype "bidirectional"))
    )
    (net (code "116") (name "unconnected-(U$6-Pad88)") (class "Default")
      (node (ref "U$6") (pin "88") (pinfunction "88_88") (pintype "bidirectional"))
    )
    (net (code "117") (name "unconnected-(U$6-Pad89)") (class "Default")
      (node (ref "U$6") (pin "89") (pinfunction "89_89") (pintype "bidirectional"))
    )
    (net (code "118") (name "unconnected-(U$6-Pad90)") (class "Default")
      (node (ref "U$6") (pin "90") (pinfunction "90_90") (pintype "bidirectional"))
    )
    (net (code "119") (name "unconnected-(U$6-Pad91)") (class "Default")
      (node (ref "U$6") (pin "91") (pinfunction "91_91") (pintype "bidirectional"))
    )
    (net (code "120") (name "unconnected-(U$6-Pad93)") (class "Default")
      (node (ref "U$6") (pin "93") (pinfunction "93_93") (pintype "output"))
    )
    (net (code "121") (name "unconnected-(U$6-Pad94)") (class "Default")
      (node (ref "U$6") (pin "94") (pinfunction "94_94") (pintype "input"))
    )
    (net (code "122") (name "unconnected-(U$9-Pad1)") (class "Default")
      (node (ref "U$9") (pin "1") (pinfunction "1_1") (pintype "input"))
    )
    (net (code "123") (name "unconnected-(U$9-Pad2)") (class "Default")
      (node (ref "U$9") (pin "2") (pinfunction "2_2") (pintype "input"))
    )
    (net (code "124") (name "unconnected-(U$9-Pad3)") (class "Default")
      (node (ref "U$9") (pin "3") (pinfunction "3_3") (pintype "input"))
    )
    (net (code "125") (name "unconnected-(U$9-SHELL-PadSHL)") (class "Default")
      (node (ref "U$9") (pin "SHL") (pinfunction "SHELL_SHL") (pintype "input"))
    )
    (net (code "126") (name "unconnected-(U$11-Pad1)") (class "Default")
      (node (ref "U$11") (pin "1") (pinfunction "1_1") (pintype "input"))
    )
    (net (code "127") (name "unconnected-(U$11-Pad2)") (class "Default")
      (node (ref "U$11") (pin "2") (pinfunction "2_2") (pintype "input"))
    )
    (net (code "128") (name "unconnected-(U$11-Pad3)") (class "Default")
      (node (ref "U$11") (pin "3") (pinfunction "3_3") (pintype "input"))
    )
    (net (code "129") (name "unconnected-(U$11-SHELL-PadSHL)") (class "Default")
      (node (ref "U$11") (pin "SHL") (pinfunction "SHELL_SHL") (pintype "input"))
    )
    (net (code "130") (name "unconnected-(U$20-Pad1)") (class "Default")
      (node (ref "U$20") (pin "1") (pinfunction "1_1") (pintype "input"))
    )
    (net (code "131") (name "unconnected-(U$20-Pad2)") (class "Default")
      (node (ref "U$20") (pin "2") (pinfunction "2_2") (pintype "input"))
    )
    (net (code "132") (name "unconnected-(U$20-Pad3)") (class "Default")
      (node (ref "U$20") (pin "3") (pinfunction "3_3") (pintype "input"))
    )
    (net (code "133") (name "unconnected-(U$20-SHELL-PadSHL)") (class "Default")
      (node (ref "U$20") (pin "SHL") (pinfunction "SHELL_SHL") (pintype "input"))
    )
  )
)
